# LionIRVT-DAC.net
KiCad netlist of a schematic drawn in Altium Designer
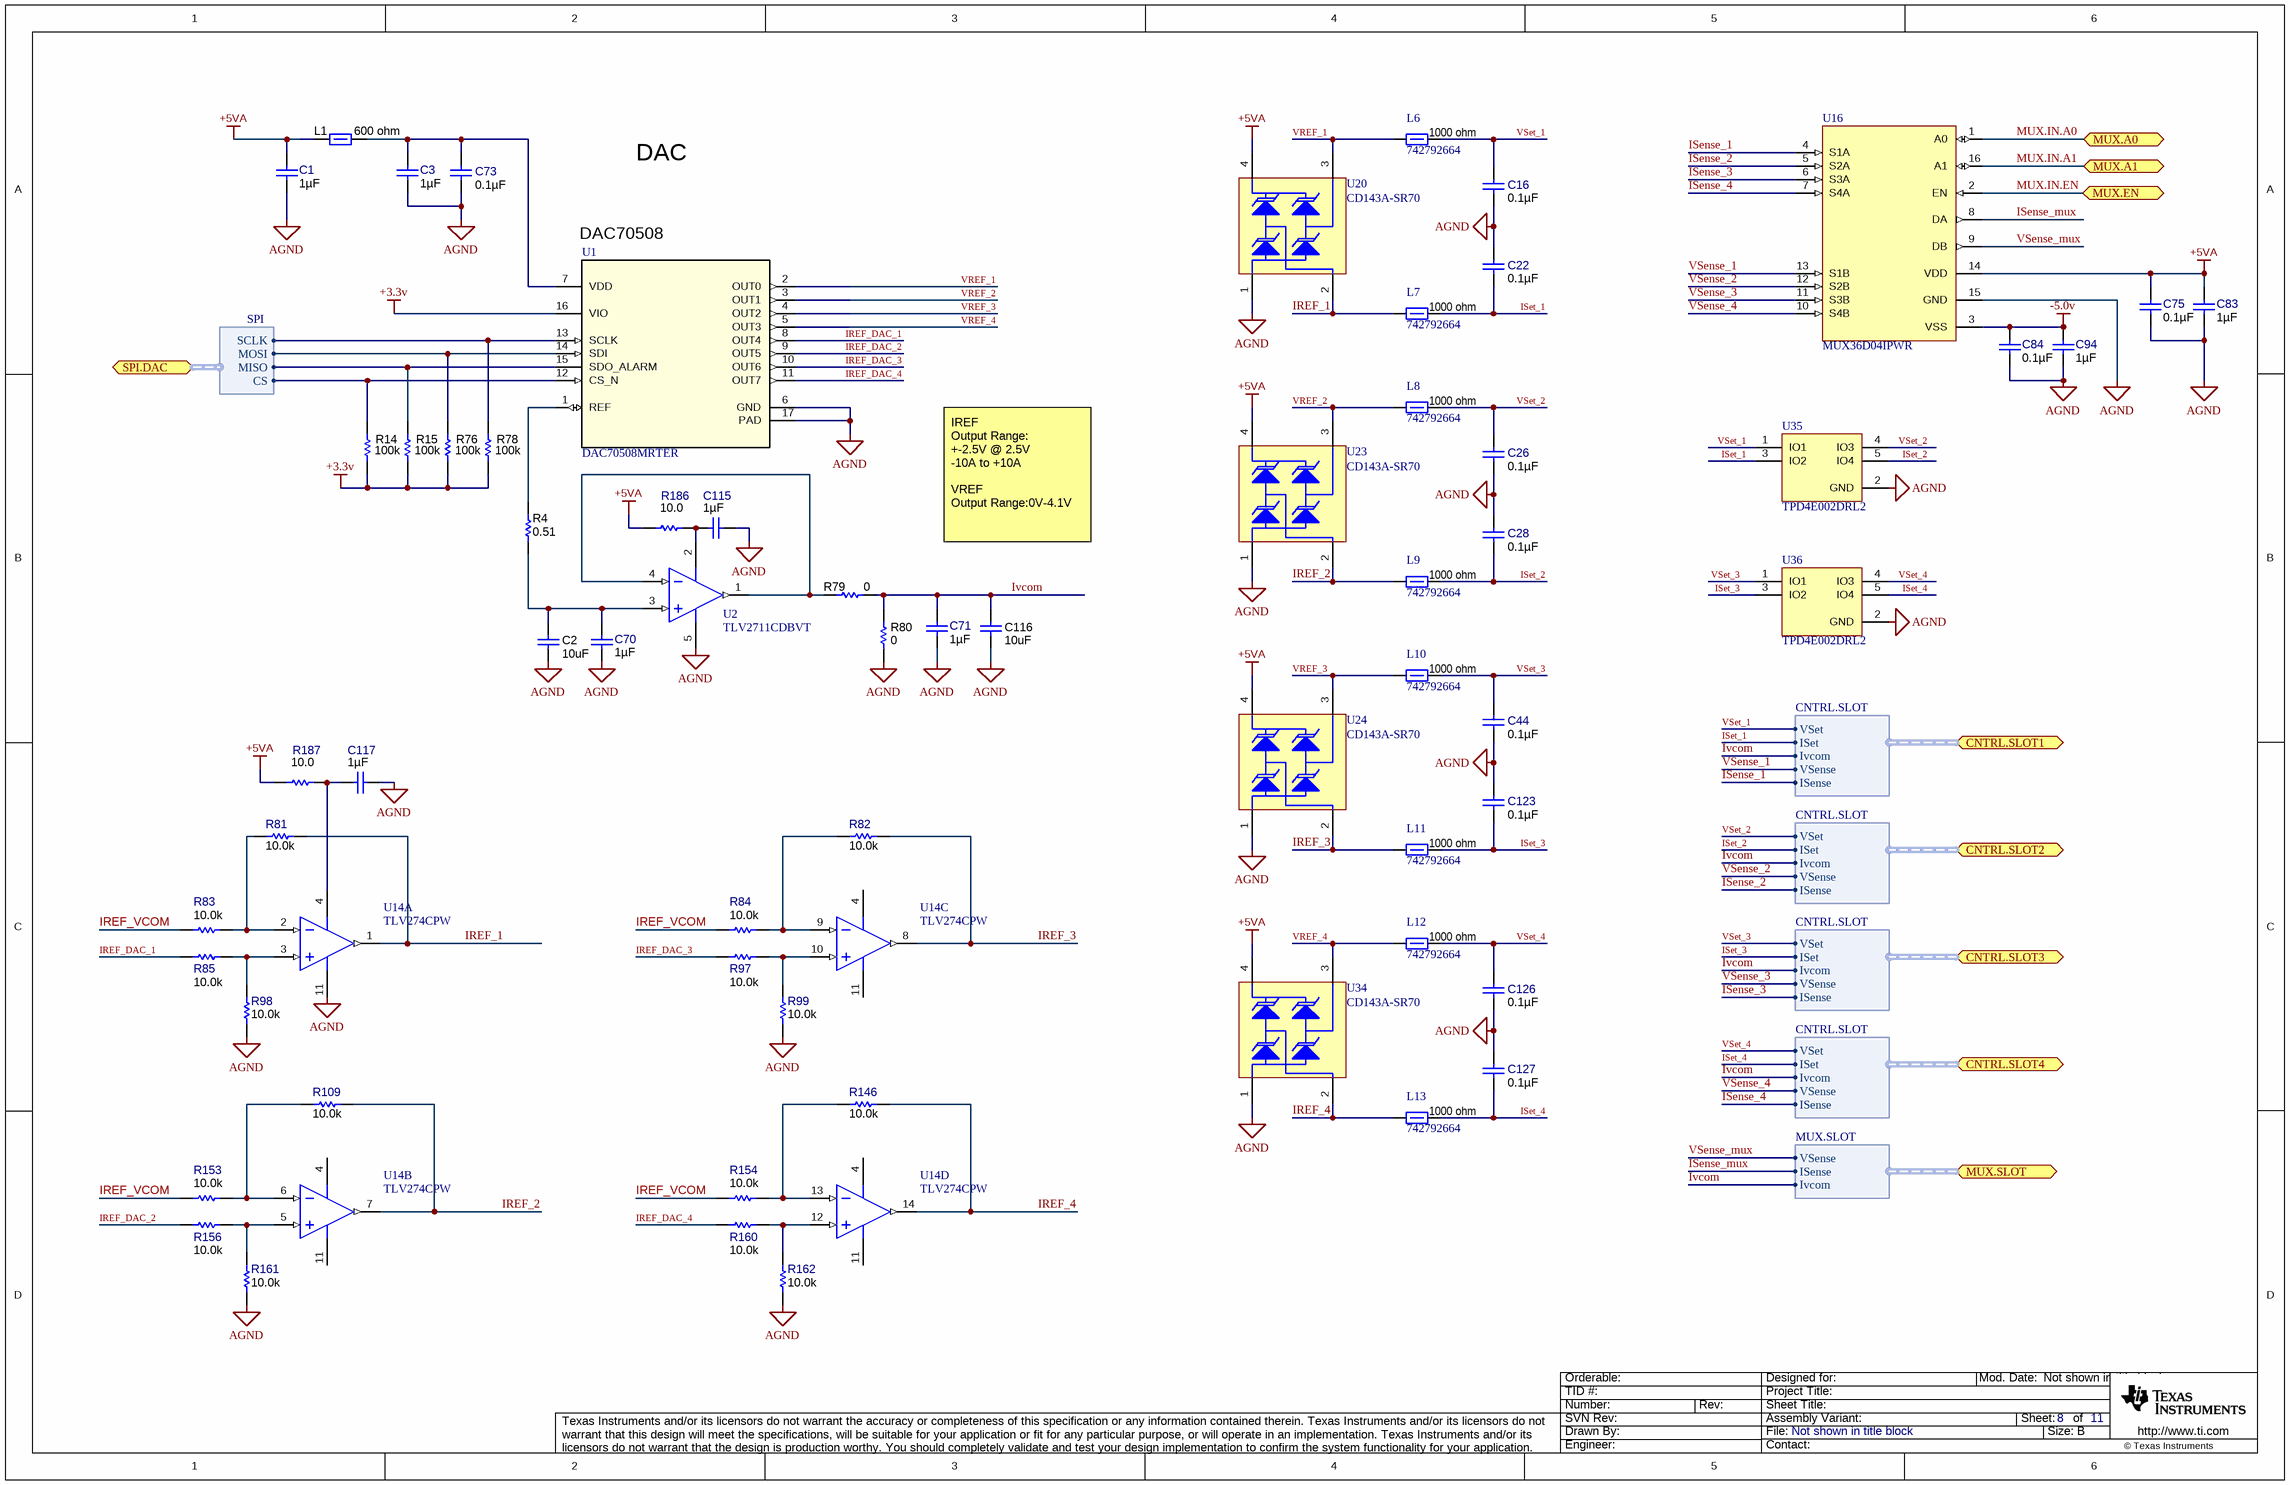
[diagram p0: LionIRVT-DAC.SchDoc]

(export (version "E")
  (design (tool "Eeschema 10.0.6"))
  (components
    (comp (ref "C1")
      (value "C0603C105K3RACTU")
      (footprint "0603C")
      (description "CAP, CERM, 1 µF, 25 V, +/- 10%, X7R, 0603")
      (fields
        (field (name "VALUEDISPLAYED") "1µF")
        (field (name "MANUFACTURER") "Kemet")
        (field (name "PUBLISHER") "Texas Instruments")
      )
      (libsource (lib "PMP40182") (part "C0603C105K3RACTU"))
    )
    (comp (ref "C2")
      (value "Capacitor")
      (footprint "0805_HV")
      (description "CAP, CERM, 10 uF, 35 V, +/- 10%, X6S, 0805")
      (fields
        (field (name "PARTNUMBER") "GRM21BC8YA106KE11L")
        (field (name "VALUEDISPLAYED") "10uF")
        (field (name "MANUFACTURER") "MuRata")
        (field (name "PUBLISHER") "Texas Instruments")
      )
      (libsource (lib "PWR578A") (part "CMP-0008273-1"))
    )
    (comp (ref "C3")
      (value "C0603C105K3RACTU")
      (footprint "0603C")
      (description "CAP, CERM, 1 µF, 25 V, +/- 10%, X7R, 0603")
      (fields
        (field (name "VALUEDISPLAYED") "1µF")
        (field (name "MANUFACTURER") "Kemet")
        (field (name "PUBLISHER") "Texas Instruments")
      )
      (libsource (lib "PMP40182") (part "C0603C105K3RACTU"))
    )
    (comp (ref "C16")
      (value "C0603C104J3RACTU")
      (footprint "0603C")
      (description "CAP, CERM, 0.1 µF, 25 V, +/- 5%, X7R, 0603")
      (fields
        (field (name "VALUEDISPLAYED") "0.1µF")
        (field (name "MANUFACTURER") "Kemet")
        (field (name "PUBLISHER") "Texas Instruments")
      )
      (libsource (lib "Capacitor_Ceramic") (part "C0603C104J3RACTU"))
    )
    (comp (ref "C22")
      (value "C0603C104J3RACTU")
      (footprint "0603C")
      (description "CAP, CERM, 0.1 µF, 25 V, +/- 5%, X7R, 0603")
      (fields
        (field (name "VALUEDISPLAYED") "0.1µF")
        (field (name "MANUFACTURER") "Kemet")
        (field (name "PUBLISHER") "Texas Instruments")
      )
      (libsource (lib "Capacitor_Ceramic") (part "C0603C104J3RACTU"))
    )
    (comp (ref "C26")
      (value "C0603C104J3RACTU")
      (footprint "0603C")
      (description "CAP, CERM, 0.1 µF, 25 V, +/- 5%, X7R, 0603")
      (fields
        (field (name "VALUEDISPLAYED") "0.1µF")
        (field (name "MANUFACTURER") "Kemet")
        (field (name "PUBLISHER") "Texas Instruments")
      )
      (libsource (lib "Capacitor_Ceramic") (part "C0603C104J3RACTU"))
    )
    (comp (ref "C28")
      (value "C0603C104J3RACTU")
      (footprint "0603C")
      (description "CAP, CERM, 0.1 µF, 25 V, +/- 5%, X7R, 0603")
      (fields
        (field (name "VALUEDISPLAYED") "0.1µF")
        (field (name "MANUFACTURER") "Kemet")
        (field (name "PUBLISHER") "Texas Instruments")
      )
      (libsource (lib "Capacitor_Ceramic") (part "C0603C104J3RACTU"))
    )
    (comp (ref "C44")
      (value "C0603C104J3RACTU")
      (footprint "0603C")
      (description "CAP, CERM, 0.1 µF, 25 V, +/- 5%, X7R, 0603")
      (fields
        (field (name "VALUEDISPLAYED") "0.1µF")
        (field (name "MANUFACTURER") "Kemet")
        (field (name "PUBLISHER") "Texas Instruments")
      )
      (libsource (lib "Capacitor_Ceramic") (part "C0603C104J3RACTU"))
    )
    (comp (ref "C70")
      (value "C0603C105K3RACTU")
      (footprint "0603C")
      (description "CAP, CERM, 1 µF, 25 V, +/- 10%, X7R, 0603")
      (fields
        (field (name "VALUEDISPLAYED") "1µF")
        (field (name "MANUFACTURER") "Kemet")
        (field (name "PUBLISHER") "Texas Instruments")
      )
      (libsource (lib "PMP40182") (part "C0603C105K3RACTU"))
    )
    (comp (ref "C71")
      (value "C0603C105K3RACTU")
      (footprint "0603C")
      (description "CAP, CERM, 1 µF, 25 V, +/- 10%, X7R, 0603")
      (fields
        (field (name "VALUEDISPLAYED") "1µF")
        (field (name "MANUFACTURER") "Kemet")
        (field (name "PUBLISHER") "Texas Instruments")
      )
      (libsource (lib "PMP40182") (part "C0603C105K3RACTU"))
    )
    (comp (ref "C73")
      (value "C0603C104J3RACTU")
      (footprint "0603C")
      (description "CAP, CERM, 0.1 µF, 25 V, +/- 5%, X7R, 0603")
      (fields
        (field (name "VALUEDISPLAYED") "0.1µF")
        (field (name "MANUFACTURER") "Kemet")
        (field (name "PUBLISHER") "Texas Instruments")
      )
      (libsource (lib "Capacitor_Ceramic") (part "C0603C104J3RACTU"))
    )
    (comp (ref "C75")
      (value "C0603C104J3RACTU")
      (footprint "0603C")
      (description "CAP, CERM, 0.1 µF, 25 V, +/- 5%, X7R, 0603")
      (fields
        (field (name "VALUEDISPLAYED") "0.1µF")
        (field (name "MANUFACTURER") "Kemet")
        (field (name "PUBLISHER") "Texas Instruments")
      )
      (libsource (lib "Capacitor_Ceramic") (part "C0603C104J3RACTU"))
    )
    (comp (ref "C83")
      (value "C0603C105K3RACTU")
      (footprint "0603C")
      (description "CAP, CERM, 1 µF, 25 V, +/- 10%, X7R, 0603")
      (fields
        (field (name "VALUEDISPLAYED") "1µF")
        (field (name "MANUFACTURER") "Kemet")
        (field (name "PUBLISHER") "Texas Instruments")
      )
      (libsource (lib "PMP40182") (part "C0603C105K3RACTU"))
    )
    (comp (ref "C84")
      (value "C0603C104J3RACTU")
      (footprint "0603C")
      (description "CAP, CERM, 0.1 µF, 25 V, +/- 5%, X7R, 0603")
      (fields
        (field (name "VALUEDISPLAYED") "0.1µF")
        (field (name "MANUFACTURER") "Kemet")
        (field (name "PUBLISHER") "Texas Instruments")
      )
      (libsource (lib "Capacitor_Ceramic") (part "C0603C104J3RACTU"))
    )
    (comp (ref "C94")
      (value "C0603C105K3RACTU")
      (footprint "0603C")
      (description "CAP, CERM, 1 µF, 25 V, +/- 10%, X7R, 0603")
      (fields
        (field (name "VALUEDISPLAYED") "1µF")
        (field (name "MANUFACTURER") "Kemet")
        (field (name "PUBLISHER") "Texas Instruments")
      )
      (libsource (lib "PMP40182") (part "C0603C105K3RACTU"))
    )
    (comp (ref "C115")
      (value "C0603C105K3RACTU")
      (footprint "0603C")
      (description "CAP, CERM, 1 µF, 25 V, +/- 10%, X7R, 0603")
      (fields
        (field (name "VALUEDISPLAYED") "1µF")
        (field (name "MANUFACTURER") "Kemet")
        (field (name "PUBLISHER") "Texas Instruments")
      )
      (libsource (lib "Capacitor_Ceramic") (part "C0603C105K3RACTU"))
    )
    (comp (ref "C116")
      (value "Capacitor")
      (footprint "0805_HV")
      (description "CAP, CERM, 10 uF, 35 V, +/- 10%, X6S, 0805")
      (fields
        (field (name "PARTNUMBER") "GRM21BC8YA106KE11L")
        (field (name "VALUEDISPLAYED") "10uF")
        (field (name "MANUFACTURER") "MuRata")
        (field (name "PUBLISHER") "Texas Instruments")
      )
      (libsource (lib "PWR578A") (part "CMP-0008273-1"))
    )
    (comp (ref "C117")
      (value "C0603C105K3RACTU")
      (footprint "0603C")
      (description "CAP, CERM, 1 µF, 25 V, +/- 10%, X7R, 0603")
      (fields
        (field (name "VALUEDISPLAYED") "1µF")
        (field (name "MANUFACTURER") "Kemet")
        (field (name "PUBLISHER") "Texas Instruments")
      )
      (libsource (lib "Capacitor_Ceramic") (part "C0603C105K3RACTU"))
    )
    (comp (ref "C123")
      (value "C0603C104J3RACTU")
      (footprint "0603C")
      (description "CAP, CERM, 0.1 µF, 25 V, +/- 5%, X7R, 0603")
      (fields
        (field (name "VALUEDISPLAYED") "0.1µF")
        (field (name "MANUFACTURER") "Kemet")
        (field (name "PUBLISHER") "Texas Instruments")
      )
      (libsource (lib "Capacitor_Ceramic") (part "C0603C104J3RACTU"))
    )
    (comp (ref "C126")
      (value "C0603C104J3RACTU")
      (footprint "0603C")
      (description "CAP, CERM, 0.1 µF, 25 V, +/- 5%, X7R, 0603")
      (fields
        (field (name "VALUEDISPLAYED") "0.1µF")
        (field (name "MANUFACTURER") "Kemet")
        (field (name "PUBLISHER") "Texas Instruments")
      )
      (libsource (lib "Capacitor_Ceramic") (part "C0603C104J3RACTU"))
    )
    (comp (ref "C127")
      (value "C0603C104J3RACTU")
      (footprint "0603C")
      (description "CAP, CERM, 0.1 µF, 25 V, +/- 5%, X7R, 0603")
      (fields
        (field (name "VALUEDISPLAYED") "0.1µF")
        (field (name "MANUFACTURER") "Kemet")
        (field (name "PUBLISHER") "Texas Instruments")
      )
      (libsource (lib "Capacitor_Ceramic") (part "C0603C104J3RACTU"))
    )
    (comp (ref "L1")
      (value "600 ohm")
      (footprint "0603L")
      (description "Ferrite Bead, 600 ohm @ 100 MHz, 1 A, 0603")
      (fields
        (field (name "PARTNUMBER") "742792651")
        (field (name "MANUFACTURER") "Wurth Elektronik")
        (field (name "PUBLISHER") "Texas Instruments")
      )
      (libsource (lib "SV601272A") (part "Ferrite_Bead"))
    )
    (comp (ref "L6")
      (value "742792664")
      (footprint "0603")
      (description "SMD EMI Suppression Ferrite Bead WE-CBF, Z = 1000 Ohm")
      (libsource (lib "PWR578A") (part "PAS-IND-INDUCTOR-2"))
    )
    (comp (ref "L7")
      (value "742792664")
      (footprint "0603")
      (description "SMD EMI Suppression Ferrite Bead WE-CBF, Z = 1000 Ohm")
      (libsource (lib "PWR578A") (part "PAS-IND-INDUCTOR-2"))
    )
    (comp (ref "L8")
      (value "742792664")
      (footprint "0603")
      (description "SMD EMI Suppression Ferrite Bead WE-CBF, Z = 1000 Ohm")
      (libsource (lib "PWR578A") (part "PAS-IND-INDUCTOR-2"))
    )
    (comp (ref "L9")
      (value "742792664")
      (footprint "0603")
      (description "SMD EMI Suppression Ferrite Bead WE-CBF, Z = 1000 Ohm")
      (libsource (lib "PWR578A") (part "PAS-IND-INDUCTOR-2"))
    )
    (comp (ref "L10")
      (value "742792664")
      (footprint "0603")
      (description "SMD EMI Suppression Ferrite Bead WE-CBF, Z = 1000 Ohm")
      (libsource (lib "PWR578A") (part "PAS-IND-INDUCTOR-2"))
    )
    (comp (ref "L11")
      (value "742792664")
      (footprint "0603")
      (description "SMD EMI Suppression Ferrite Bead WE-CBF, Z = 1000 Ohm")
      (libsource (lib "PWR578A") (part "PAS-IND-INDUCTOR-2"))
    )
    (comp (ref "L12")
      (value "742792664")
      (footprint "0603")
      (description "SMD EMI Suppression Ferrite Bead WE-CBF, Z = 1000 Ohm")
      (libsource (lib "PWR578A") (part "PAS-IND-INDUCTOR-2"))
    )
    (comp (ref "L13")
      (value "742792664")
      (footprint "0603")
      (description "SMD EMI Suppression Ferrite Bead WE-CBF, Z = 1000 Ohm")
      (libsource (lib "PWR578A") (part "PAS-IND-INDUCTOR-2"))
    )
    (comp (ref "R4")
      (value "Resistor")
      (footprint "0603R")
      (description "RES, 0.51, 1%, 0.1 W, AEC-Q200 Grade 1, 0603")
      (fields
        (field (name "PARTNUMBER") "ERJ-3RQFR51V")
        (field (name "VALUEDISPLAYED") "0.51")
        (field (name "MANUFACTURER") "Panasonic")
        (field (name "PUBLISHER") "Texas Instruments")
      )
      (libsource (lib "SV601272A") (part "CMP-0022717-2"))
    )
    (comp (ref "R14")
      (value "Resistor")
      (footprint "0603R")
      (description "RES, 100 k, 1%, 0.1 W, AEC-Q200 Grade 0, 0603")
      (fields
        (field (name "PARTNUMBER") "CRCW0603100KFKEA")
        (field (name "MANUFACTURER") "Vishay-Dale")
        (field (name "VALUEDISPLAYED") "100k")
      )
      (libsource (lib "PMP40182") (part "CMP-0021990-4"))
    )
    (comp (ref "R15")
      (value "Resistor")
      (footprint "0603R")
      (description "RES, 100 k, 1%, 0.1 W, AEC-Q200 Grade 0, 0603")
      (fields
        (field (name "PARTNUMBER") "CRCW0603100KFKEA")
        (field (name "MANUFACTURER") "Vishay-Dale")
        (field (name "VALUEDISPLAYED") "100k")
      )
      (libsource (lib "PMP40182") (part "CMP-0021990-4"))
    )
    (comp (ref "R76")
      (value "Resistor")
      (footprint "0603R")
      (description "RES, 100 k, 1%, 0.1 W, AEC-Q200 Grade 0, 0603")
      (fields
        (field (name "PARTNUMBER") "CRCW0603100KFKEA")
        (field (name "MANUFACTURER") "Vishay-Dale")
        (field (name "VALUEDISPLAYED") "100k")
      )
      (libsource (lib "PMP40182") (part "CMP-0021990-4"))
    )
    (comp (ref "R78")
      (value "Resistor")
      (footprint "0603R")
      (description "RES, 100 k, 1%, 0.1 W, AEC-Q200 Grade 0, 0603")
      (fields
        (field (name "PARTNUMBER") "CRCW0603100KFKEA")
        (field (name "MANUFACTURER") "Vishay-Dale")
        (field (name "VALUEDISPLAYED") "100k")
      )
      (libsource (lib "PMP40182") (part "CMP-0021990-4"))
    )
    (comp (ref "R79")
      (value "Resistor")
      (footprint "0603R")
      (description "RES, 0, 5%, 0.1 W, 0603")
      (fields
        (field (name "PARTNUMBER") "ERJ-3GEY0R00V")
        (field (name "MANUFACTURER") "Panasonic")
        (field (name "VALUEDISPLAYED") "0")
        (field (name "PUBLISHER") "Texas Instruments")
      )
      (libsource (lib "PMP40182") (part "CMP-0025874-3"))
    )
    (comp (ref "R80")
      (value "Resistor")
      (footprint "0603R")
      (description "RES, 0, 5%, 0.1 W, 0603")
      (fields
        (field (name "PARTNUMBER") "ERJ-3GEY0R00V")
        (field (name "MANUFACTURER") "Panasonic")
        (field (name "VALUEDISPLAYED") "0")
        (field (name "PUBLISHER") "Texas Instruments")
      )
      (libsource (lib "PMP40182") (part "CMP-0025874-3"))
    )
    (comp (ref "R81")
      (value "RC0603FR-0710KL")
      (footprint "0603R")
      (description "RES, 10.0 k, 1%, 0.1 W, 0603")
      (fields
        (field (name "VALUEDISPLAYED") "10.0k")
        (field (name "MANUFACTURER") "Yageo America")
        (field (name "PUBLISHER") "Texas Instruments")
      )
      (libsource (lib "Resistor_0603") (part "RC0603FR-0710KL"))
    )
    (comp (ref "R82")
      (value "RC0603FR-0710KL")
      (footprint "0603R")
      (description "RES, 10.0 k, 1%, 0.1 W, 0603")
      (fields
        (field (name "VALUEDISPLAYED") "10.0k")
        (field (name "MANUFACTURER") "Yageo America")
        (field (name "PUBLISHER") "Texas Instruments")
      )
      (libsource (lib "Resistor_0603") (part "RC0603FR-0710KL"))
    )
    (comp (ref "R83")
      (value "RC0603FR-0710KL")
      (footprint "0603R")
      (description "RES, 10.0 k, 1%, 0.1 W, 0603")
      (fields
        (field (name "VALUEDISPLAYED") "10.0k")
        (field (name "MANUFACTURER") "Yageo America")
        (field (name "PUBLISHER") "Texas Instruments")
      )
      (libsource (lib "Resistor_0603") (part "RC0603FR-0710KL"))
    )
    (comp (ref "R84")
      (value "RC0603FR-0710KL")
      (footprint "0603R")
      (description "RES, 10.0 k, 1%, 0.1 W, 0603")
      (fields
        (field (name "VALUEDISPLAYED") "10.0k")
        (field (name "MANUFACTURER") "Yageo America")
        (field (name "PUBLISHER") "Texas Instruments")
      )
      (libsource (lib "Resistor_0603") (part "RC0603FR-0710KL"))
    )
    (comp (ref "R85")
      (value "RC0603FR-0710KL")
      (footprint "0603R")
      (description "RES, 10.0 k, 1%, 0.1 W, 0603")
      (fields
        (field (name "VALUEDISPLAYED") "10.0k")
        (field (name "MANUFACTURER") "Yageo America")
        (field (name "PUBLISHER") "Texas Instruments")
      )
      (libsource (lib "Resistor_0603") (part "RC0603FR-0710KL"))
    )
    (comp (ref "R97")
      (value "RC0603FR-0710KL")
      (footprint "0603R")
      (description "RES, 10.0 k, 1%, 0.1 W, 0603")
      (fields
        (field (name "VALUEDISPLAYED") "10.0k")
        (field (name "MANUFACTURER") "Yageo America")
        (field (name "PUBLISHER") "Texas Instruments")
      )
      (libsource (lib "Resistor_0603") (part "RC0603FR-0710KL"))
    )
    (comp (ref "R98")
      (value "RC0603FR-0710KL")
      (footprint "0603R")
      (description "RES, 10.0 k, 1%, 0.1 W, 0603")
      (fields
        (field (name "VALUEDISPLAYED") "10.0k")
        (field (name "MANUFACTURER") "Yageo America")
        (field (name "PUBLISHER") "Texas Instruments")
      )
      (libsource (lib "Resistor_0603") (part "RC0603FR-0710KL"))
    )
    (comp (ref "R99")
      (value "RC0603FR-0710KL")
      (footprint "0603R")
      (description "RES, 10.0 k, 1%, 0.1 W, 0603")
      (fields
        (field (name "VALUEDISPLAYED") "10.0k")
        (field (name "MANUFACTURER") "Yageo America")
        (field (name "PUBLISHER") "Texas Instruments")
      )
      (libsource (lib "Resistor_0603") (part "RC0603FR-0710KL"))
    )
    (comp (ref "R109")
      (value "RC0603FR-0710KL")
      (footprint "0603R")
      (description "RES, 10.0 k, 1%, 0.1 W, 0603")
      (fields
        (field (name "VALUEDISPLAYED") "10.0k")
        (field (name "MANUFACTURER") "Yageo America")
        (field (name "PUBLISHER") "Texas Instruments")
      )
      (libsource (lib "Resistor_0603") (part "RC0603FR-0710KL"))
    )
    (comp (ref "R146")
      (value "RC0603FR-0710KL")
      (footprint "0603R")
      (description "RES, 10.0 k, 1%, 0.1 W, 0603")
      (fields
        (field (name "VALUEDISPLAYED") "10.0k")
        (field (name "MANUFACTURER") "Yageo America")
        (field (name "PUBLISHER") "Texas Instruments")
      )
      (libsource (lib "Resistor_0603") (part "RC0603FR-0710KL"))
    )
    (comp (ref "R153")
      (value "RC0603FR-0710KL")
      (footprint "0603R")
      (description "RES, 10.0 k, 1%, 0.1 W, 0603")
      (fields
        (field (name "VALUEDISPLAYED") "10.0k")
        (field (name "MANUFACTURER") "Yageo America")
        (field (name "PUBLISHER") "Texas Instruments")
      )
      (libsource (lib "Resistor_0603") (part "RC0603FR-0710KL"))
    )
    (comp (ref "R154")
      (value "RC0603FR-0710KL")
      (footprint "0603R")
      (description "RES, 10.0 k, 1%, 0.1 W, 0603")
      (fields
        (field (name "VALUEDISPLAYED") "10.0k")
        (field (name "MANUFACTURER") "Yageo America")
        (field (name "PUBLISHER") "Texas Instruments")
      )
      (libsource (lib "Resistor_0603") (part "RC0603FR-0710KL"))
    )
    (comp (ref "R156")
      (value "RC0603FR-0710KL")
      (footprint "0603R")
      (description "RES, 10.0 k, 1%, 0.1 W, 0603")
      (fields
        (field (name "VALUEDISPLAYED") "10.0k")
        (field (name "MANUFACTURER") "Yageo America")
        (field (name "PUBLISHER") "Texas Instruments")
      )
      (libsource (lib "Resistor_0603") (part "RC0603FR-0710KL"))
    )
    (comp (ref "R160")
      (value "RC0603FR-0710KL")
      (footprint "0603R")
      (description "RES, 10.0 k, 1%, 0.1 W, 0603")
      (fields
        (field (name "VALUEDISPLAYED") "10.0k")
        (field (name "MANUFACTURER") "Yageo America")
        (field (name "PUBLISHER") "Texas Instruments")
      )
      (libsource (lib "Resistor_0603") (part "RC0603FR-0710KL"))
    )
    (comp (ref "R161")
      (value "RC0603FR-0710KL")
      (footprint "0603R")
      (description "RES, 10.0 k, 1%, 0.1 W, 0603")
      (fields
        (field (name "VALUEDISPLAYED") "10.0k")
        (field (name "MANUFACTURER") "Yageo America")
        (field (name "PUBLISHER") "Texas Instruments")
      )
      (libsource (lib "Resistor_0603") (part "RC0603FR-0710KL"))
    )
    (comp (ref "R162")
      (value "RC0603FR-0710KL")
      (footprint "0603R")
      (description "RES, 10.0 k, 1%, 0.1 W, 0603")
      (fields
        (field (name "VALUEDISPLAYED") "10.0k")
        (field (name "MANUFACTURER") "Yageo America")
        (field (name "PUBLISHER") "Texas Instruments")
      )
      (libsource (lib "Resistor_0603") (part "RC0603FR-0710KL"))
    )
    (comp (ref "R186")
      (value "RC0603FR-0710RL")
      (footprint "0603R")
      (description "RES, 10.0, 1%, 0.1 W, 0603")
      (fields
        (field (name "VALUEDISPLAYED") "10.0")
        (field (name "MANUFACTURER") "Yageo America")
        (field (name "PUBLISHER") "Texas Instruments")
      )
      (libsource (lib "Resistor_0603") (part "RC0603FR-0710RL"))
    )
    (comp (ref "R187")
      (value "RC0603FR-0710RL")
      (footprint "0603R")
      (description "RES, 10.0, 1%, 0.1 W, 0603")
      (fields
        (field (name "VALUEDISPLAYED") "10.0")
        (field (name "MANUFACTURER") "Yageo America")
        (field (name "PUBLISHER") "Texas Instruments")
      )
      (libsource (lib "Resistor_0603") (part "RC0603FR-0710RL"))
    )
    (comp (ref "U1")
      (value "DAC70508MRTER")
      (footprint "RTE0016D")
      (description "No Description Available")
      (fields
        (field (name "PARTNUMBER") "DAC70508ZRTER")
        (field (name "MANUFACTURER") "Texas Instruments")
        (field (name "COPYRIGHT") "Copyright (C) 2018 Accelerated Designs. All rights reserved")
      )
      (libsource (lib "PWR578A") (part "DAC70508MRTER"))
    )
    (comp (ref "U2")
      (value "TLV2711CDBVT")
      (footprint "DBV0005A_M")
      (fields (field (name "MANUFACTURER") "Texas Instruments"))
      (libsource (lib "Altium Content Vault") (part "TI-TLV27X1DBV5"))
    )
    (comp (ref "U14")
      (value "TLV274CPW")
      (footprint "PW0014A_M")
      (fields (field (name "MANUFACTURER") "Texas Instruments"))
      (libsource (lib "Altium Content Vault") (part "TI-TLC_TLV_TLC1079-14"))
    )
    (comp (ref "U16")
      (value "MUX36D04IPWR")
      (footprint "PW0016A_N")
      (description "No Description Available")
      (fields
        (field (name "MANUFACTURER") "Texas Instruments")
        (field (name "COPYRIGHT") "Copyright (C) 2018 Accelerated Designs. All rights reserved")
      )
      (libsource (lib "PWR578A") (part "MUX36D04IPWR"))
    )
    (comp (ref "U20")
      (value "CD143A-SR70")
      (footprint "SOT143B")
      (description "TVS DIODE 7V SOT143")
      (fields (field (name "MANUFACTURER") "Bourns"))
      (libsource (lib "PWR578A") (part "CD143A-SR70"))
    )
    (comp (ref "U23")
      (value "CD143A-SR70")
      (footprint "SOT143B")
      (description "TVS DIODE 7V SOT143")
      (fields (field (name "MANUFACTURER") "Bourns"))
      (libsource (lib "PWR578A") (part "CD143A-SR70"))
    )
    (comp (ref "U24")
      (value "CD143A-SR70")
      (footprint "SOT143B")
      (description "TVS DIODE 7V SOT143")
      (fields (field (name "MANUFACTURER") "Bourns"))
      (libsource (lib "PWR578A") (part "CD143A-SR70"))
    )
    (comp (ref "U34")
      (value "CD143A-SR70")
      (footprint "SOT143B")
      (description "TVS DIODE 7V SOT143")
      (fields (field (name "MANUFACTURER") "Bourns"))
      (libsource (lib "PWR578A") (part "CD143A-SR70"))
    )
    (comp (ref "U35")
      (value "TPD4E002DRL2")
      (footprint "DRL0005A_N")
      (fields (field (name "MANUFACTURER") "Texas Instruments"))
      (libsource (lib "Altium Content Vault") (part "TI-TPD4E002-SOT_DRL-5"))
    )
    (comp (ref "U36")
      (value "TPD4E002DRL2")
      (footprint "DRL0005A_N")
      (fields (field (name "MANUFACTURER") "Texas Instruments"))
      (libsource (lib "Altium Content Vault") (part "TI-TPD4E002-SOT_DRL-5"))
    )
  )
  (nets
    (net (code "4") (name "+3.3v") (class "Default")
      (node (ref "R14") (pin "1") (pinfunction "1_1") (pintype "passive"))
      (node (ref "R15") (pin "1") (pinfunction "1_1") (pintype "passive"))
      (node (ref "R76") (pin "1") (pinfunction "1_1") (pintype "passive"))
      (node (ref "R78") (pin "1") (pinfunction "1_1") (pintype "passive"))
      (node (ref "U1") (pin "16") (pinfunction "VIO_16") (pintype "power_in"))
    )
    (net (code "5") (name "+5VA") (class "Default")
      (node (ref "C1") (pin "1") (pinfunction "1_1") (pintype "passive"))
      (node (ref "C75") (pin "1") (pinfunction "1_1") (pintype "passive"))
      (node (ref "C83") (pin "2") (pinfunction "2_2") (pintype "passive"))
      (node (ref "L1") (pin "1") (pinfunction "1_1") (pintype "passive"))
      (node (ref "R186") (pin "2") (pinfunction "2_2") (pintype "passive"))
      (node (ref "R187") (pin "2") (pinfunction "2_2") (pintype "passive"))
      (node (ref "U16") (pin "14") (pinfunction "VDD_14") (pintype "power_in"))
      (node (ref "U20") (pin "4") (pintype "passive"))
      (node (ref "U23") (pin "4") (pintype "passive"))
      (node (ref "U24") (pin "4") (pintype "passive"))
      (node (ref "U34") (pin "4") (pintype "passive"))
    )
    (net (code "6") (name "-5.0v") (class "Default")
      (node (ref "C84") (pin "1") (pinfunction "1_1") (pintype "passive"))
      (node (ref "C94") (pin "2") (pinfunction "2_2") (pintype "passive"))
      (node (ref "U16") (pin "3") (pinfunction "VSS_3") (pintype "power_in"))
    )
    (net (code "7") (name "/IREF_1") (class "Default")
      (node (ref "L7") (pin "1") (pinfunction "1_1") (pintype "passive"))
      (node (ref "R81") (pin "2") (pinfunction "2_2") (pintype "passive"))
      (node (ref "U14") (pin "1") (pinfunction "OUT1_1") (pintype "output"))
      (node (ref "U20") (pin "2") (pintype "passive"))
    )
    (net (code "8") (name "/IREF_2") (class "Default")
      (node (ref "L9") (pin "1") (pinfunction "1_1") (pintype "passive"))
      (node (ref "R109") (pin "2") (pinfunction "2_2") (pintype "passive"))
      (node (ref "U14") (pin "7") (pinfunction "OUT2_7") (pintype "output"))
      (node (ref "U23") (pin "2") (pintype "passive"))
    )
    (net (code "9") (name "/IREF_3") (class "Default")
      (node (ref "L11") (pin "1") (pinfunction "1_1") (pintype "passive"))
      (node (ref "R82") (pin "2") (pinfunction "2_2") (pintype "passive"))
      (node (ref "U14") (pin "8") (pinfunction "OUT3_8") (pintype "output"))
      (node (ref "U24") (pin "2") (pintype "passive"))
    )
    (net (code "10") (name "/IREF_4") (class "Default")
      (node (ref "L13") (pin "1") (pinfunction "1_1") (pintype "passive"))
      (node (ref "R146") (pin "2") (pinfunction "2_2") (pintype "passive"))
      (node (ref "U14") (pin "14") (pinfunction "OUT4_14") (pintype "output"))
      (node (ref "U34") (pin "2") (pintype "passive"))
    )
    (net (code "11") (name "/IREF_DAC_1") (class "Default")
      (node (ref "R85") (pin "1") (pinfunction "1_1") (pintype "passive"))
      (node (ref "U1") (pin "8") (pinfunction "OUT4_8") (pintype "output"))
    )
    (net (code "12") (name "/IREF_DAC_2") (class "Default")
      (node (ref "R156") (pin "1") (pinfunction "1_1") (pintype "passive"))
      (node (ref "U1") (pin "9") (pinfunction "OUT5_9") (pintype "output"))
    )
    (net (code "13") (name "/IREF_DAC_3") (class "Default")
      (node (ref "R97") (pin "1") (pinfunction "1_1") (pintype "passive"))
      (node (ref "U1") (pin "10") (pinfunction "OUT6_10") (pintype "output"))
    )
    (net (code "14") (name "/IREF_DAC_4") (class "Default")
      (node (ref "R160") (pin "1") (pinfunction "1_1") (pintype "passive"))
      (node (ref "U1") (pin "11") (pinfunction "OUT7_11") (pintype "output"))
    )
    (net (code "15") (name "/IREF_VCOM") (class "Default")
      (node (ref "R153") (pin "1") (pinfunction "1_1") (pintype "passive"))
      (node (ref "R154") (pin "1") (pinfunction "1_1") (pintype "passive"))
      (node (ref "R83") (pin "1") (pinfunction "1_1") (pintype "passive"))
      (node (ref "R84") (pin "1") (pinfunction "1_1") (pintype "passive"))
    )
    (net (code "16") (name "/ISense_1") (class "Default")
      (node (ref "U16") (pin "4") (pinfunction "S1A_4") (pintype "input"))
    )
    (net (code "17") (name "/ISense_2") (class "Default")
      (node (ref "U16") (pin "5") (pinfunction "S2A_5") (pintype "input"))
    )
    (net (code "18") (name "/ISense_3") (class "Default")
      (node (ref "U16") (pin "6") (pinfunction "S3A_6") (pintype "input"))
    )
    (net (code "19") (name "/ISense_4") (class "Default")
      (node (ref "U16") (pin "7") (pinfunction "S4A_7") (pintype "input"))
    )
    (net (code "20") (name "/ISense_mux") (class "Default")
      (node (ref "U16") (pin "8") (pinfunction "DA_8") (pintype "output"))
    )
    (net (code "21") (name "/ISet_1") (class "Default")
      (node (ref "C22") (pin "1") (pinfunction "1_1") (pintype "passive"))
      (node (ref "L7") (pin "2") (pinfunction "2_2") (pintype "passive"))
      (node (ref "U35") (pin "3") (pinfunction "IO2_3") (pintype "passive"))
    )
    (net (code "22") (name "/ISet_2") (class "Default")
      (node (ref "C28") (pin "1") (pinfunction "1_1") (pintype "passive"))
      (node (ref "L9") (pin "2") (pinfunction "2_2") (pintype "passive"))
      (node (ref "U35") (pin "5") (pinfunction "IO4_5") (pintype "passive"))
    )
    (net (code "23") (name "/ISet_3") (class "Default")
      (node (ref "C123") (pin "1") (pinfunction "1_1") (pintype "passive"))
      (node (ref "L11") (pin "2") (pinfunction "2_2") (pintype "passive"))
      (node (ref "U36") (pin "3") (pinfunction "IO2_3") (pintype "passive"))
    )
    (net (code "24") (name "/ISet_4") (class "Default")
      (node (ref "C127") (pin "1") (pinfunction "1_1") (pintype "passive"))
      (node (ref "L13") (pin "2") (pinfunction "2_2") (pintype "passive"))
      (node (ref "U36") (pin "5") (pinfunction "IO4_5") (pintype "passive"))
    )
    (net (code "25") (name "/Ivcom") (class "Default")
      (node (ref "C116") (pin "1") (pinfunction "1_1") (pintype "passive"))
      (node (ref "C71") (pin "1") (pinfunction "1_1") (pintype "passive"))
      (node (ref "R79") (pin "2") (pinfunction "2_2") (pintype "passive"))
      (node (ref "R80") (pin "2") (pinfunction "2_2") (pintype "passive"))
    )
    (net (code "26") (name "/MUX.IN.A0") (class "Default")
      (node (ref "U16") (pin "1") (pinfunction "A0_1") (pintype "bidirectional"))
    )
    (net (code "27") (name "/MUX.IN.A1") (class "Default")
      (node (ref "U16") (pin "16") (pinfunction "A1_16") (pintype "bidirectional"))
    )
    (net (code "28") (name "/MUX.IN.EN") (class "Default")
      (node (ref "U16") (pin "2") (pinfunction "EN_2") (pintype "input"))
    )
    (net (code "29") (name "/VREF_1") (class "Default")
      (node (ref "L6") (pin "1") (pinfunction "1_1") (pintype "passive"))
      (node (ref "U1") (pin "2") (pinfunction "OUT0_2") (pintype "output"))
      (node (ref "U20") (pin "3") (pintype "passive"))
    )
    (net (code "30") (name "/VREF_2") (class "Default")
      (node (ref "L8") (pin "1") (pinfunction "1_1") (pintype "passive"))
      (node (ref "U1") (pin "3") (pinfunction "OUT1_3") (pintype "output"))
      (node (ref "U23") (pin "3") (pintype "passive"))
    )
    (net (code "31") (name "/VREF_3") (class "Default")
      (node (ref "L10") (pin "1") (pinfunction "1_1") (pintype "passive"))
      (node (ref "U1") (pin "4") (pinfunction "OUT2_4") (pintype "output"))
      (node (ref "U24") (pin "3") (pintype "passive"))
    )
    (net (code "32") (name "/VREF_4") (class "Default")
      (node (ref "L12") (pin "1") (pinfunction "1_1") (pintype "passive"))
      (node (ref "U1") (pin "5") (pinfunction "OUT3_5") (pintype "output"))
      (node (ref "U34") (pin "3") (pintype "passive"))
    )
    (net (code "33") (name "/VSense_1") (class "Default")
      (node (ref "U16") (pin "13") (pinfunction "S1B_13") (pintype "input"))
    )
    (net (code "34") (name "/VSense_2") (class "Default")
      (node (ref "U16") (pin "12") (pinfunction "S2B_12") (pintype "input"))
    )
    (net (code "35") (name "/VSense_3") (class "Default")
      (node (ref "U16") (pin "11") (pinfunction "S3B_11") (pintype "input"))
    )
    (net (code "36") (name "/VSense_4") (class "Default")
      (node (ref "U16") (pin "10") (pinfunction "S4B_10") (pintype "input"))
    )
    (net (code "37") (name "/VSense_mux") (class "Default")
      (node (ref "U16") (pin "9") (pinfunction "DB_9") (pintype "output"))
    )
    (net (code "38") (name "/VSet_1") (class "Default")
      (node (ref "C16") (pin "2") (pinfunction "2_2") (pintype "passive"))
      (node (ref "L6") (pin "2") (pinfunction "2_2") (pintype "passive"))
      (node (ref "U35") (pin "1") (pinfunction "IO1_1") (pintype "passive"))
    )
    (net (code "39") (name "/VSet_2") (class "Default")
      (node (ref "C26") (pin "2") (pinfunction "2_2") (pintype "passive"))
      (node (ref "L8") (pin "2") (pinfunction "2_2") (pintype "passive"))
      (node (ref "U35") (pin "4") (pinfunction "IO3_4") (pintype "passive"))
    )
    (net (code "40") (name "/VSet_3") (class "Default")
      (node (ref "C44") (pin "2") (pinfunction "2_2") (pintype "passive"))
      (node (ref "L10") (pin "2") (pinfunction "2_2") (pintype "passive"))
      (node (ref "U36") (pin "1") (pinfunction "IO1_1") (pintype "passive"))
    )
    (net (code "41") (name "/VSet_4") (class "Default")
      (node (ref "C126") (pin "2") (pinfunction "2_2") (pintype "passive"))
      (node (ref "L12") (pin "2") (pinfunction "2_2") (pintype "passive"))
      (node (ref "U36") (pin "4") (pinfunction "IO3_4") (pintype "passive"))
    )
    (net (code "45") (name "AGND") (class "Default")
      (node (ref "C1") (pin "2") (pinfunction "2_2") (pintype "passive"))
      (node (ref "C115") (pin "1") (pinfunction "1_1") (pintype "passive"))
      (node (ref "C116") (pin "2") (pinfunction "2_2") (pintype "passive"))
      (node (ref "C117") (pin "1") (pinfunction "1_1") (pintype "passive"))
      (node (ref "C123") (pin "2") (pinfunction "2_2") (pintype "passive"))
      (node (ref "C126") (pin "1") (pinfunction "1_1") (pintype "passive"))
      (node (ref "C127") (pin "2") (pinfunction "2_2") (pintype "passive"))
      (node (ref "C16") (pin "1") (pinfunction "1_1") (pintype "passive"))
      (node (ref "C2") (pin "2") (pinfunction "2_2") (pintype "passive"))
      (node (ref "C22") (pin "2") (pinfunction "2_2") (pintype "passive"))
      (node (ref "C26") (pin "1") (pinfunction "1_1") (pintype "passive"))
      (node (ref "C28") (pin "2") (pinfunction "2_2") (pintype "passive"))
      (node (ref "C3") (pin "2") (pinfunction "2_2") (pintype "passive"))
      (node (ref "C44") (pin "1") (pinfunction "1_1") (pintype "passive"))
      (node (ref "C70") (pin "2") (pinfunction "2_2") (pintype "passive"))
      (node (ref "C71") (pin "2") (pinfunction "2_2") (pintype "passive"))
      (node (ref "C73") (pin "1") (pinfunction "1_1") (pintype "passive"))
      (node (ref "C75") (pin "2") (pinfunction "2_2") (pintype "passive"))
      (node (ref "C83") (pin "1") (pinfunction "1_1") (pintype "passive"))
      (node (ref "C84") (pin "2") (pinfunction "2_2") (pintype "passive"))
      (node (ref "C94") (pin "1") (pinfunction "1_1") (pintype "passive"))
      (node (ref "R161") (pin "2") (pinfunction "2_2") (pintype "passive"))
      (node (ref "R162") (pin "2") (pinfunction "2_2") (pintype "passive"))
      (node (ref "R80") (pin "1") (pinfunction "1_1") (pintype "passive"))
      (node (ref "R98") (pin "2") (pinfunction "2_2") (pintype "passive"))
      (node (ref "R99") (pin "2") (pinfunction "2_2") (pintype "passive"))
      (node (ref "U1") (pin "17") (pinfunction "PAD_17") (pintype "power_in"))
      (node (ref "U1") (pin "6") (pinfunction "GND_6") (pintype "power_in"))
      (node (ref "U14") (pin "11") (pinfunction "GND_11") (pintype "power_in"))
      (node (ref "U16") (pin "15") (pinfunction "GND_15") (pintype "power_in"))
      (node (ref "U2") (pin "5") (pinfunction "VDD-/GND_5") (pintype "power_in"))
      (node (ref "U20") (pin "1") (pintype "passive"))
      (node (ref "U23") (pin "1") (pintype "passive"))
      (node (ref "U24") (pin "1") (pintype "passive"))
      (node (ref "U34") (pin "1") (pintype "passive"))
      (node (ref "U35") (pin "2") (pinfunction "GND_2") (pintype "power_in"))
      (node (ref "U36") (pin "2") (pinfunction "GND_2") (pintype "power_in"))
    )
    (net (code "46") (name "Net-(U1-CS_N)") (class "Default")
      (node (ref "R14") (pin "2") (pinfunction "2_2") (pintype "passive"))
      (node (ref "U1") (pin "12") (pinfunction "CS_N_12") (pintype "input"))
    )
    (net (code "47") (name "Net-(U1-REF)") (class "Default")
      (node (ref "R4") (pin "2") (pinfunction "2_2") (pintype "passive"))
      (node (ref "U1") (pin "1") (pinfunction "REF_1") (pintype "bidirectional"))
    )
    (net (code "48") (name "Net-(U1-SCLK)") (class "Default")
      (node (ref "R78") (pin "2") (pinfunction "2_2") (pintype "passive"))
      (node (ref "U1") (pin "13") (pinfunction "SCLK_13") (pintype "input"))
    )
    (net (code "49") (name "Net-(U1-SDI)") (class "Default")
      (node (ref "R76") (pin "2") (pinfunction "2_2") (pintype "passive"))
      (node (ref "U1") (pin "14") (pinfunction "SDI_14") (pintype "input"))
    )
    (net (code "50") (name "Net-(U1-SDO_ALARM)") (class "Default")
      (node (ref "R15") (pin "2") (pinfunction "2_2") (pintype "passive"))
      (node (ref "U1") (pin "15") (pinfunction "SDO_ALARM_15") (pintype "tri_state"))
    )
    (net (code "51") (name "Net-(U1-VDD)") (class "Default")
      (node (ref "C3") (pin "1") (pinfunction "1_1") (pintype "passive"))
      (node (ref "C73") (pin "2") (pinfunction "2_2") (pintype "passive"))
      (node (ref "L1") (pin "2") (pinfunction "2_2") (pintype "passive"))
      (node (ref "U1") (pin "7") (pinfunction "VDD_7") (pintype "power_in"))
    )
    (net (code "52") (name "Net-(U2-IN+)") (class "Default")
      (node (ref "C2") (pin "1") (pinfunction "1_1") (pintype "passive"))
      (node (ref "C70") (pin "1") (pinfunction "1_1") (pintype "passive"))
      (node (ref "R4") (pin "1") (pinfunction "1_1") (pintype "passive"))
      (node (ref "U2") (pin "3") (pinfunction "IN+_3") (pintype "input"))
    )
    (net (code "53") (name "Net-(U2-IN-)") (class "Default")
      (node (ref "R79") (pin "1") (pinfunction "1_1") (pintype "passive"))
      (node (ref "U2") (pin "1") (pinfunction "OUT_1") (pintype "output"))
      (node (ref "U2") (pin "4") (pinfunction "IN-_4") (pintype "input"))
    )
    (net (code "54") (name "Net-(U2-VDD+)") (class "Default")
      (node (ref "C115") (pin "2") (pinfunction "2_2") (pintype "passive"))
      (node (ref "R186") (pin "1") (pinfunction "1_1") (pintype "passive"))
      (node (ref "U2") (pin "2") (pinfunction "VDD+_2") (pintype "power_in"))
    )
    (net (code "55") (name "Net-(U14A-IN1+)") (class "Default")
      (node (ref "R85") (pin "2") (pinfunction "2_2") (pintype "passive"))
      (node (ref "R98") (pin "1") (pinfunction "1_1") (pintype "passive"))
      (node (ref "U14") (pin "3") (pinfunction "IN1+_3") (pintype "input"))
    )
    (net (code "56") (name "Net-(U14A-IN1-)") (class "Default")
      (node (ref "R81") (pin "1") (pinfunction "1_1") (pintype "passive"))
      (node (ref "R83") (pin "2") (pinfunction "2_2") (pintype "passive"))
      (node (ref "U14") (pin "2") (pinfunction "IN1-_2") (pintype "input"))
    )
    (net (code "57") (name "Net-(U14A-VDD)") (class "Default")
      (node (ref "C117") (pin "2") (pinfunction "2_2") (pintype "passive"))
      (node (ref "R187") (pin "1") (pinfunction "1_1") (pintype "passive"))
      (node (ref "U14") (pin "4") (pinfunction "VDD_4") (pintype "power_in"))
    )
    (net (code "58") (name "Net-(U14B-IN2+)") (class "Default")
      (node (ref "R156") (pin "2") (pinfunction "2_2") (pintype "passive"))
      (node (ref "R161") (pin "1") (pinfunction "1_1") (pintype "passive"))
      (node (ref "U14") (pin "5") (pinfunction "IN2+_5") (pintype "input"))
    )
    (net (code "59") (name "Net-(U14B-IN2-)") (class "Default")
      (node (ref "R109") (pin "1") (pinfunction "1_1") (pintype "passive"))
      (node (ref "R153") (pin "2") (pinfunction "2_2") (pintype "passive"))
      (node (ref "U14") (pin "6") (pinfunction "IN2-_6") (pintype "input"))
    )
    (net (code "60") (name "Net-(U14C-IN3+)") (class "Default")
      (node (ref "R97") (pin "2") (pinfunction "2_2") (pintype "passive"))
      (node (ref "R99") (pin "1") (pinfunction "1_1") (pintype "passive"))
      (node (ref "U14") (pin "10") (pinfunction "IN3+_10") (pintype "input"))
    )
    (net (code "61") (name "Net-(U14C-IN3-)") (class "Default")
      (node (ref "R82") (pin "1") (pinfunction "1_1") (pintype "passive"))
      (node (ref "R84") (pin "2") (pinfunction "2_2") (pintype "passive"))
      (node (ref "U14") (pin "9") (pinfunction "IN3-_9") (pintype "input"))
    )
    (net (code "62") (name "Net-(U14D-IN4+)") (class "Default")
      (node (ref "R160") (pin "2") (pinfunction "2_2") (pintype "passive"))
      (node (ref "R162") (pin "1") (pinfunction "1_1") (pintype "passive"))
      (node (ref "U14") (pin "12") (pinfunction "IN4+_12") (pintype "input"))
    )
    (net (code "63") (name "Net-(U14D-IN4-)") (class "Default")
      (node (ref "R146") (pin "1") (pinfunction "1_1") (pintype "passive"))
      (node (ref "R154") (pin "2") (pinfunction "2_2") (pintype "passive"))
      (node (ref "U14") (pin "13") (pinfunction "IN4-_13") (pintype "input"))
    )
    (net (code "64") (name "unconnected-(U14B-GND-Pad11)") (class "Default")
      (node (ref "U14") (pin "11") (pinfunction "GND_11") (pintype "power_in"))
    )
    (net (code "65") (name "unconnected-(U14B-VDD-Pad4)") (class "Default")
      (node (ref "U14") (pin "4") (pinfunction "VDD_4") (pintype "power_in"))
    )
    (net (code "66") (name "unconnected-(U14C-GND-Pad11)") (class "Default")
      (node (ref "U14") (pin "11") (pinfunction "GND_11") (pintype "power_in"))
    )
    (net (code "67") (name "unconnected-(U14C-VDD-Pad4)") (class "Default")
      (node (ref "U14") (pin "4") (pinfunction "VDD_4") (pintype "power_in"))
    )
    (net (code "68") (name "unconnected-(U14D-GND-Pad11)") (class "Default")
      (node (ref "U14") (pin "11") (pinfunction "GND_11") (pintype "power_in"))
    )
    (net (code "69") (name "unconnected-(U14D-VDD-Pad4)") (class "Default")
      (node (ref "U14") (pin "4") (pinfunction "VDD_4") (pintype "power_in"))
    )
  )
)
